# TCA_CLK_DIST.net
KiCad netlist of a schematic drawn in Altium Designer
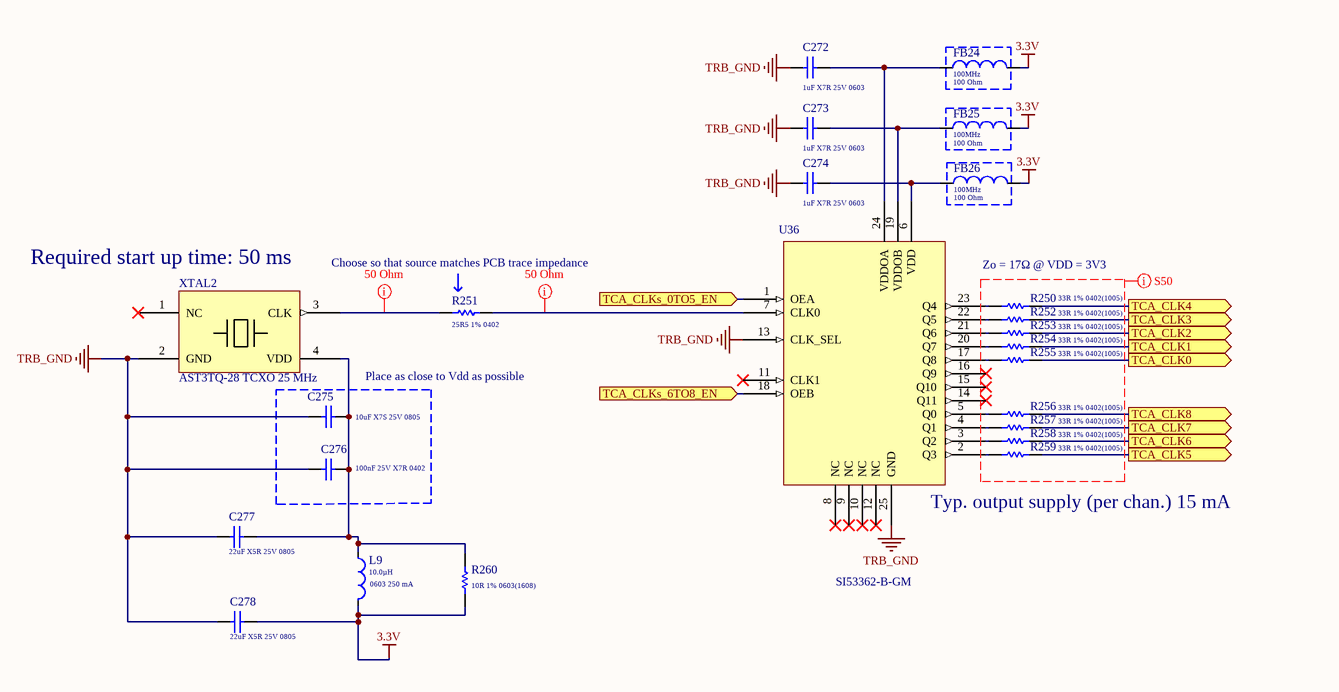
[diagram p0: TCA_CLK_DIST.SchDoc]

(export (version "E")
  (design (tool "Eeschema 10.0.6"))
  (components
    (comp (ref "C272")
      (value "Cap_Murata_GCJ188R71E105KA01J_1uF")
      (footprint "Cap_Murata_GCJ188R71E105KA01J_1uF")
      (description "CAP CER 1uF 25V X7R 0603")
      (fields (field (name "CAPACITANCE") "1uF X7R 25V 0603"))
      (libsource (lib "Cap_Murata_GCJ188R71E105KA01J_1uF") (part "Cap_Murata_GCJ188R71E105KA01J_1uF"))
    )
    (comp (ref "C273")
      (value "Cap_Murata_GCJ188R71E105KA01J_1uF")
      (footprint "Cap_Murata_GCJ188R71E105KA01J_1uF")
      (description "CAP CER 1uF 25V X7R 0603")
      (fields (field (name "CAPACITANCE") "1uF X7R 25V 0603"))
      (libsource (lib "Cap_Murata_GCJ188R71E105KA01J_1uF") (part "Cap_Murata_GCJ188R71E105KA01J_1uF"))
    )
    (comp (ref "C274")
      (value "Cap_Murata_GCJ188R71E105KA01J_1uF")
      (footprint "Cap_Murata_GCJ188R71E105KA01J_1uF")
      (description "CAP CER 1uF 25V X7R 0603")
      (fields (field (name "CAPACITANCE") "1uF X7R 25V 0603"))
      (libsource (lib "Cap_Murata_GCJ188R71E105KA01J_1uF") (part "Cap_Murata_GCJ188R71E105KA01J_1uF"))
    )
    (comp (ref "C275")
      (value "Cap_Murata_ GRM21BC71E106ME11L_10uF")
      (footprint "Cap_Murata_ GRM21BC71E106ME11L_10uF")
      (description "CAP CER 10uF 25V X7R 0805")
      (fields (field (name "CAPACITANCE") "10uF X7S 25V 0805"))
      (libsource (lib "Cap_Murata_ GRM21BC71E106ME11L_10uF") (part "Cap_Murata_ GRM21BC71E106ME11L_10uF"))
    )
    (comp (ref "C276")
      (value "Cap_Taiyo_Yuden_TMK105B7104KV-FR_100nF")
      (footprint "Cap_Taiyo_Yuden_TMK105B7104KV-FR_100nF")
      (description "CAP CER 100nF 25V X7R 0402")
      (fields (field (name "CAPACITANCE") "100nF 25V X7R 0402"))
      (libsource (lib "Cap_Taiyo_Yuden_TMK105B7104KV-FR_100nF") (part "Cap_Taiyo_Yuden_TMK105B7104KV-FR_100nF"))
    )
    (comp (ref "C277")
      (value "Cap_Murata_GRT21BR61E226ME13L_22uF")
      (footprint "Cap_Murata_GRT21BR61E226ME13L_22uF")
      (description "CAP CER 22uF 25V X5R 0805")
      (fields (field (name "CAPACITANCE") "22uF X5R 25V 0805"))
      (libsource (lib "Cap_Murata_GRT21BR61E226ME13L_22uF") (part "Cap_Murata_GRT21BR61E226ME13L_22uF"))
    )
    (comp (ref "C278")
      (value "Cap_Murata_GRT21BR61E226ME13L_22uF")
      (footprint "Cap_Murata_GRT21BR61E226ME13L_22uF")
      (description "CAP CER 22uF 25V X5R 0805")
      (fields (field (name "CAPACITANCE") "22uF X5R 25V 0805"))
      (libsource (lib "Cap_Murata_GRT21BR61E226ME13L_22uF") (part "Cap_Murata_GRT21BR61E226ME13L_22uF"))
    )
    (comp (ref "FB24")
      (value "742792731")
      (footprint "FB_Wurth_Electronics_742792731_100Ohms")
      (description "FB SMD 100 OHM 25% 1.2A 0402")
      (fields (field (name "MEASURING FREQUENCY") "100MHz") (field (name "IMPEDANCE") "100 Ohm"))
      (libsource (lib "FB_Wurth_Electronics_742792731_100Ohms") (part "FB_Wurth_Electronics_742792731_100Ohms"))
    )
    (comp (ref "FB25")
      (value "742792731")
      (footprint "FB_Wurth_Electronics_742792731_100Ohms")
      (description "FB SMD 100 OHM 25% 1.2A 0402")
      (fields (field (name "MEASURING FREQUENCY") "100MHz") (field (name "IMPEDANCE") "100 Ohm"))
      (libsource (lib "FB_Wurth_Electronics_742792731_100Ohms") (part "FB_Wurth_Electronics_742792731_100Ohms"))
    )
    (comp (ref "FB26")
      (value "742792731")
      (footprint "FB_Wurth_Electronics_742792731_100Ohms")
      (description "FB SMD 100 OHM 25% 1.2A 0402")
      (fields (field (name "MEASURING FREQUENCY") "100MHz") (field (name "IMPEDANCE") "100 Ohm"))
      (libsource (lib "FB_Wurth_Electronics_742792731_100Ohms") (part "FB_Wurth_Electronics_742792731_100Ohms"))
    )
    (comp (ref "L9")
      (value "0603 250 mA")
      (footprint "TDK_MLZ1608M100WT_0")
      (description "IND 10µH Shielded Multilayer Inductor 250mA 1.365 Ohm Max 0603 (1608 Metric)")
      (fields
        (field (name "PART NUMBER") "MLZ1608M100WT")
        (field (name "MANUFACTURER") "TDK")
        (field (name "INDUCTANCE") "10.0µH")
      )
      (libsource (lib "Ind_TDK_MLZ1608M100WT_10uH") (part "Ind_TDK_MLZ1608M100WT_eec"))
    )
    (comp (ref "R250")
      (value "33R 1% 0402(1005)")
      (footprint "RESC0402(1005)_L")
      (description "33R 0.063W 1% 0402 (1005 Metric)  SMD")
      (fields (field (name "TOLERANCE") "1 %") (field (name "POWER") "0.063 W"))
      (libsource (lib "Altium Content Vault") (part "RES"))
    )
    (comp (ref "R251")
      (value "25R5 1% 0402")
      (footprint "RESC0402(1005)_L")
      (description "25R5 0.063W 1% 0402 (1005 Metric)  SMD")
      (fields (field (name "TOLERANCE") "1 %") (field (name "POWER") "0.063 W"))
      (libsource (lib "Altium Content Vault") (part "RES"))
    )
    (comp (ref "R252")
      (value "33R 1% 0402(1005)")
      (footprint "RESC0402(1005)_L")
      (description "33R 0.063W 1% 0402 (1005 Metric)  SMD")
      (fields (field (name "TOLERANCE") "1 %") (field (name "POWER") "0.063 W"))
      (libsource (lib "Altium Content Vault") (part "RES"))
    )
    (comp (ref "R253")
      (value "33R 1% 0402(1005)")
      (footprint "RESC0402(1005)_L")
      (description "33R 0.063W 1% 0402 (1005 Metric)  SMD")
      (fields (field (name "TOLERANCE") "1 %") (field (name "POWER") "0.063 W"))
      (libsource (lib "Altium Content Vault") (part "RES"))
    )
    (comp (ref "R254")
      (value "33R 1% 0402(1005)")
      (footprint "RESC0402(1005)_L")
      (description "33R 0.063W 1% 0402 (1005 Metric)  SMD")
      (fields (field (name "TOLERANCE") "1 %") (field (name "POWER") "0.063 W"))
      (libsource (lib "Altium Content Vault") (part "RES"))
    )
    (comp (ref "R255")
      (value "33R 1% 0402(1005)")
      (footprint "RESC0402(1005)_L")
      (description "33R 0.063W 1% 0402 (1005 Metric)  SMD")
      (fields (field (name "TOLERANCE") "1 %") (field (name "POWER") "0.063 W"))
      (libsource (lib "Altium Content Vault") (part "RES"))
    )
    (comp (ref "R256")
      (value "33R 1% 0402(1005)")
      (footprint "RESC0402(1005)_L")
      (description "33R 0.063W 1% 0402 (1005 Metric)  SMD")
      (fields (field (name "TOLERANCE") "1 %") (field (name "POWER") "0.063 W"))
      (libsource (lib "Altium Content Vault") (part "RES"))
    )
    (comp (ref "R257")
      (value "33R 1% 0402(1005)")
      (footprint "RESC0402(1005)_L")
      (description "33R 0.063W 1% 0402 (1005 Metric)  SMD")
      (fields (field (name "TOLERANCE") "1 %") (field (name "POWER") "0.063 W"))
      (libsource (lib "Altium Content Vault") (part "RES"))
    )
    (comp (ref "R258")
      (value "33R 1% 0402(1005)")
      (footprint "RESC0402(1005)_L")
      (description "33R 0.063W 1% 0402 (1005 Metric)  SMD")
      (fields (field (name "TOLERANCE") "1 %") (field (name "POWER") "0.063 W"))
      (libsource (lib "Altium Content Vault") (part "RES"))
    )
    (comp (ref "R259")
      (value "33R 1% 0402(1005)")
      (footprint "RESC0402(1005)_L")
      (description "33R 0.063W 1% 0402 (1005 Metric)  SMD")
      (fields (field (name "TOLERANCE") "1 %") (field (name "POWER") "0.063 W"))
      (libsource (lib "Altium Content Vault") (part "RES"))
    )
    (comp (ref "R260")
      (value "10R 1% 0603(1608)")
      (footprint "RESC0603(1608)_L")
      (description "10R 0.1W 1% 0603 (1608 Metric)  SMD")
      (fields (field (name "TOLERANCE") "1 %") (field (name "POWER") "0.1 W"))
      (libsource (lib "Altium Content Vault") (part "RES"))
    )
    (comp (ref "U36")
      (value "SI53362-B-GM")
      (footprint "Si53362")
      (description "Clock Buffer LVCMOS 2:12 buffer (200MHz), 2:1 LVCMOS input max, output enable (QFN24)")
      (libsource (lib "SI53362") (part "SI53362-B-GM"))
    )
    (comp (ref "XTAL2")
      (value "AST3TQ-28 TCXO 25 MHz")
      (footprint "XTAL_ASDM1-25.000MHZ-LC-T")
      (description "TCXO Oscillators 25MHz 3.3Volt LVCMOS 0.280 ppm -40C 85C")
      (libsource (lib "XTAL_Abracaon_AST3TQ-T-25.000MHz-28") (part "AST3TQ-28"))
    )
  )
  (nets
    (net (code "1") (name "/TCA_CLK0") (class "Default")
      (node (ref "R255") (pin "2") (pinfunction "2_2") (pintype "passive"))
    )
    (net (code "2") (name "/TCA_CLK1") (class "Default")
      (node (ref "R254") (pin "2") (pinfunction "2_2") (pintype "passive"))
    )
    (net (code "3") (name "/TCA_CLK2") (class "Default")
      (node (ref "R253") (pin "2") (pinfunction "2_2") (pintype "passive"))
    )
    (net (code "4") (name "/TCA_CLK3") (class "Default")
      (node (ref "R252") (pin "2") (pinfunction "2_2") (pintype "passive"))
    )
    (net (code "5") (name "/TCA_CLK4") (class "Default")
      (node (ref "R250") (pin "2") (pinfunction "2_2") (pintype "passive"))
    )
    (net (code "6") (name "/TCA_CLK5") (class "Default")
      (node (ref "R259") (pin "2") (pinfunction "2_2") (pintype "passive"))
    )
    (net (code "7") (name "/TCA_CLK6") (class "Default")
      (node (ref "R258") (pin "2") (pinfunction "2_2") (pintype "passive"))
    )
    (net (code "8") (name "/TCA_CLK7") (class "Default")
      (node (ref "R257") (pin "2") (pinfunction "2_2") (pintype "passive"))
    )
    (net (code "9") (name "/TCA_CLK8") (class "Default")
      (node (ref "R256") (pin "2") (pinfunction "2_2") (pintype "passive"))
    )
    (net (code "10") (name "/TCA_CLKs_0TO5_EN") (class "Default")
      (node (ref "U36") (pin "1") (pinfunction "OEA_1") (pintype "input"))
    )
    (net (code "11") (name "/TCA_CLKs_6TO8_EN") (class "Default")
      (node (ref "U36") (pin "18") (pinfunction "OEB_18") (pintype "input"))
    )
    (net (code "12") (name "3.3V") (class "Default")
      (node (ref "C278") (pin "2") (pinfunction "2_2") (pintype "passive"))
      (node (ref "FB24") (pin "2") (pinfunction "2_2") (pintype "passive"))
      (node (ref "FB25") (pin "2") (pinfunction "2_2") (pintype "passive"))
      (node (ref "FB26") (pin "2") (pinfunction "2_2") (pintype "passive"))
      (node (ref "L9") (pin "2") (pinfunction "2_2") (pintype "passive"))
      (node (ref "R260") (pin "1") (pinfunction "1_1") (pintype "passive"))
    )
    (net (code "13") (name "Net-(U36-CLK0)") (class "Default")
      (node (ref "R251") (pin "2") (pinfunction "2_2") (pintype "passive"))
      (node (ref "U36") (pin "7") (pinfunction "CLK0_7") (pintype "input"))
    )
    (net (code "14") (name "Net-(U36-Q0)") (class "Default")
      (node (ref "R256") (pin "1") (pinfunction "1_1") (pintype "passive"))
      (node (ref "U36") (pin "5") (pinfunction "Q0_5") (pintype "output"))
    )
    (net (code "15") (name "Net-(U36-Q1)") (class "Default")
      (node (ref "R257") (pin "1") (pinfunction "1_1") (pintype "passive"))
      (node (ref "U36") (pin "4") (pinfunction "Q1_4") (pintype "output"))
    )
    (net (code "16") (name "Net-(U36-Q2)") (class "Default")
      (node (ref "R258") (pin "1") (pinfunction "1_1") (pintype "passive"))
      (node (ref "U36") (pin "3") (pinfunction "Q2_3") (pintype "output"))
    )
    (net (code "17") (name "Net-(U36-Q3)") (class "Default")
      (node (ref "R259") (pin "1") (pinfunction "1_1") (pintype "passive"))
      (node (ref "U36") (pin "2") (pinfunction "Q3_2") (pintype "output"))
    )
    (net (code "18") (name "Net-(U36-Q4)") (class "Default")
      (node (ref "R250") (pin "1") (pinfunction "1_1") (pintype "passive"))
      (node (ref "U36") (pin "23") (pinfunction "Q4_23") (pintype "output"))
    )
    (net (code "19") (name "Net-(U36-Q5)") (class "Default")
      (node (ref "R252") (pin "1") (pinfunction "1_1") (pintype "passive"))
      (node (ref "U36") (pin "22") (pinfunction "Q5_22") (pintype "output"))
    )
    (net (code "20") (name "Net-(U36-Q6)") (class "Default")
      (node (ref "R253") (pin "1") (pinfunction "1_1") (pintype "passive"))
      (node (ref "U36") (pin "21") (pinfunction "Q6_21") (pintype "output"))
    )
    (net (code "21") (name "Net-(U36-Q7)") (class "Default")
      (node (ref "R254") (pin "1") (pinfunction "1_1") (pintype "passive"))
      (node (ref "U36") (pin "20") (pinfunction "Q7_20") (pintype "output"))
    )
    (net (code "22") (name "Net-(U36-Q8)") (class "Default")
      (node (ref "R255") (pin "1") (pinfunction "1_1") (pintype "passive"))
      (node (ref "U36") (pin "17") (pinfunction "Q8_17") (pintype "output"))
    )
    (net (code "23") (name "Net-(U36-VDD)") (class "Default")
      (node (ref "C274") (pin "1") (pinfunction "1_1") (pintype "passive"))
      (node (ref "FB26") (pin "1") (pinfunction "1_1") (pintype "passive"))
      (node (ref "U36") (pin "6") (pinfunction "VDD_6") (pintype "power_in"))
    )
    (net (code "24") (name "Net-(U36-VDDOA)") (class "Default")
      (node (ref "C272") (pin "1") (pinfunction "1_1") (pintype "passive"))
      (node (ref "FB24") (pin "1") (pinfunction "1_1") (pintype "passive"))
      (node (ref "U36") (pin "24") (pinfunction "VDDOA_24") (pintype "power_in"))
    )
    (net (code "25") (name "Net-(U36-VDDOB)") (class "Default")
      (node (ref "C273") (pin "1") (pinfunction "1_1") (pintype "passive"))
      (node (ref "FB25") (pin "1") (pinfunction "1_1") (pintype "passive"))
      (node (ref "U36") (pin "19") (pinfunction "VDDOB_19") (pintype "power_in"))
    )
    (net (code "26") (name "Net-(XTAL2-CLK)") (class "Default")
      (node (ref "R251") (pin "1") (pinfunction "1_1") (pintype "passive"))
      (node (ref "XTAL2") (pin "3") (pinfunction "CLK_3") (pintype "output"))
    )
    (net (code "27") (name "Net-(XTAL2-VDD)") (class "Default")
      (node (ref "C275") (pin "2") (pinfunction "2_2") (pintype "passive"))
      (node (ref "C276") (pin "1") (pinfunction "1_1") (pintype "passive"))
      (node (ref "C277") (pin "2") (pinfunction "2_2") (pintype "passive"))
      (node (ref "L9") (pin "1") (pinfunction "1_1") (pintype "passive"))
      (node (ref "R260") (pin "2") (pinfunction "2_2") (pintype "passive"))
      (node (ref "XTAL2") (pin "4") (pinfunction "VDD_4") (pintype "power_in"))
    )
    (net (code "28") (name "TRB_GND") (class "Default")
      (node (ref "C272") (pin "2") (pinfunction "2_2") (pintype "passive"))
      (node (ref "C273") (pin "2") (pinfunction "2_2") (pintype "passive"))
      (node (ref "C274") (pin "2") (pinfunction "2_2") (pintype "passive"))
      (node (ref "C275") (pin "1") (pinfunction "1_1") (pintype "passive"))
      (node (ref "C276") (pin "2") (pinfunction "2_2") (pintype "passive"))
      (node (ref "C277") (pin "1") (pinfunction "1_1") (pintype "passive"))
      (node (ref "C278") (pin "1") (pinfunction "1_1") (pintype "passive"))
      (node (ref "U36") (pin "13") (pinfunction "CLK_SEL_13") (pintype "input"))
      (node (ref "U36") (pin "25") (pinfunction "GND_25") (pintype "passive"))
      (node (ref "XTAL2") (pin "2") (pinfunction "GND_2") (pintype "passive"))
    )
    (net (code "29") (name "unconnected-(U36-CLK1-Pad11)") (class "Default")
      (node (ref "U36") (pin "11") (pinfunction "CLK1_11") (pintype "input+no_connect"))
    )
    (net (code "30") (name "unconnected-(U36-NC-Pad8)") (class "Default")
      (node (ref "U36") (pin "8") (pinfunction "NC_8") (pintype "passive+no_connect"))
    )
    (net (code "31") (name "unconnected-(U36-NC-Pad9)") (class "Default")
      (node (ref "U36") (pin "9") (pinfunction "NC_9") (pintype "passive+no_connect"))
    )
    (net (code "32") (name "unconnected-(U36-NC-Pad10)") (class "Default")
      (node (ref "U36") (pin "10") (pinfunction "NC_10") (pintype "passive+no_connect"))
    )
    (net (code "33") (name "unconnected-(U36-NC-Pad12)") (class "Default")
      (node (ref "U36") (pin "12") (pinfunction "NC_12") (pintype "passive+no_connect"))
    )
    (net (code "34") (name "unconnected-(U36-Q9-Pad16)") (class "Default")
      (node (ref "U36") (pin "16") (pinfunction "Q9_16") (pintype "output+no_connect"))
    )
    (net (code "35") (name "unconnected-(U36-Q10-Pad15)") (class "Default")
      (node (ref "U36") (pin "15") (pinfunction "Q10_15") (pintype "output+no_connect"))
    )
    (net (code "36") (name "unconnected-(U36-Q11-Pad14)") (class "Default")
      (node (ref "U36") (pin "14") (pinfunction "Q11_14") (pintype "output+no_connect"))
    )
    (net (code "37") (name "unconnected-(XTAL2-NC-Pad1)") (class "Default")
      (node (ref "XTAL2") (pin "1") (pinfunction "NC_1") (pintype "passive+no_connect"))
    )
  )
)
